# voiceboard.net
KiCad netlist of a schematic drawn in EAGLE
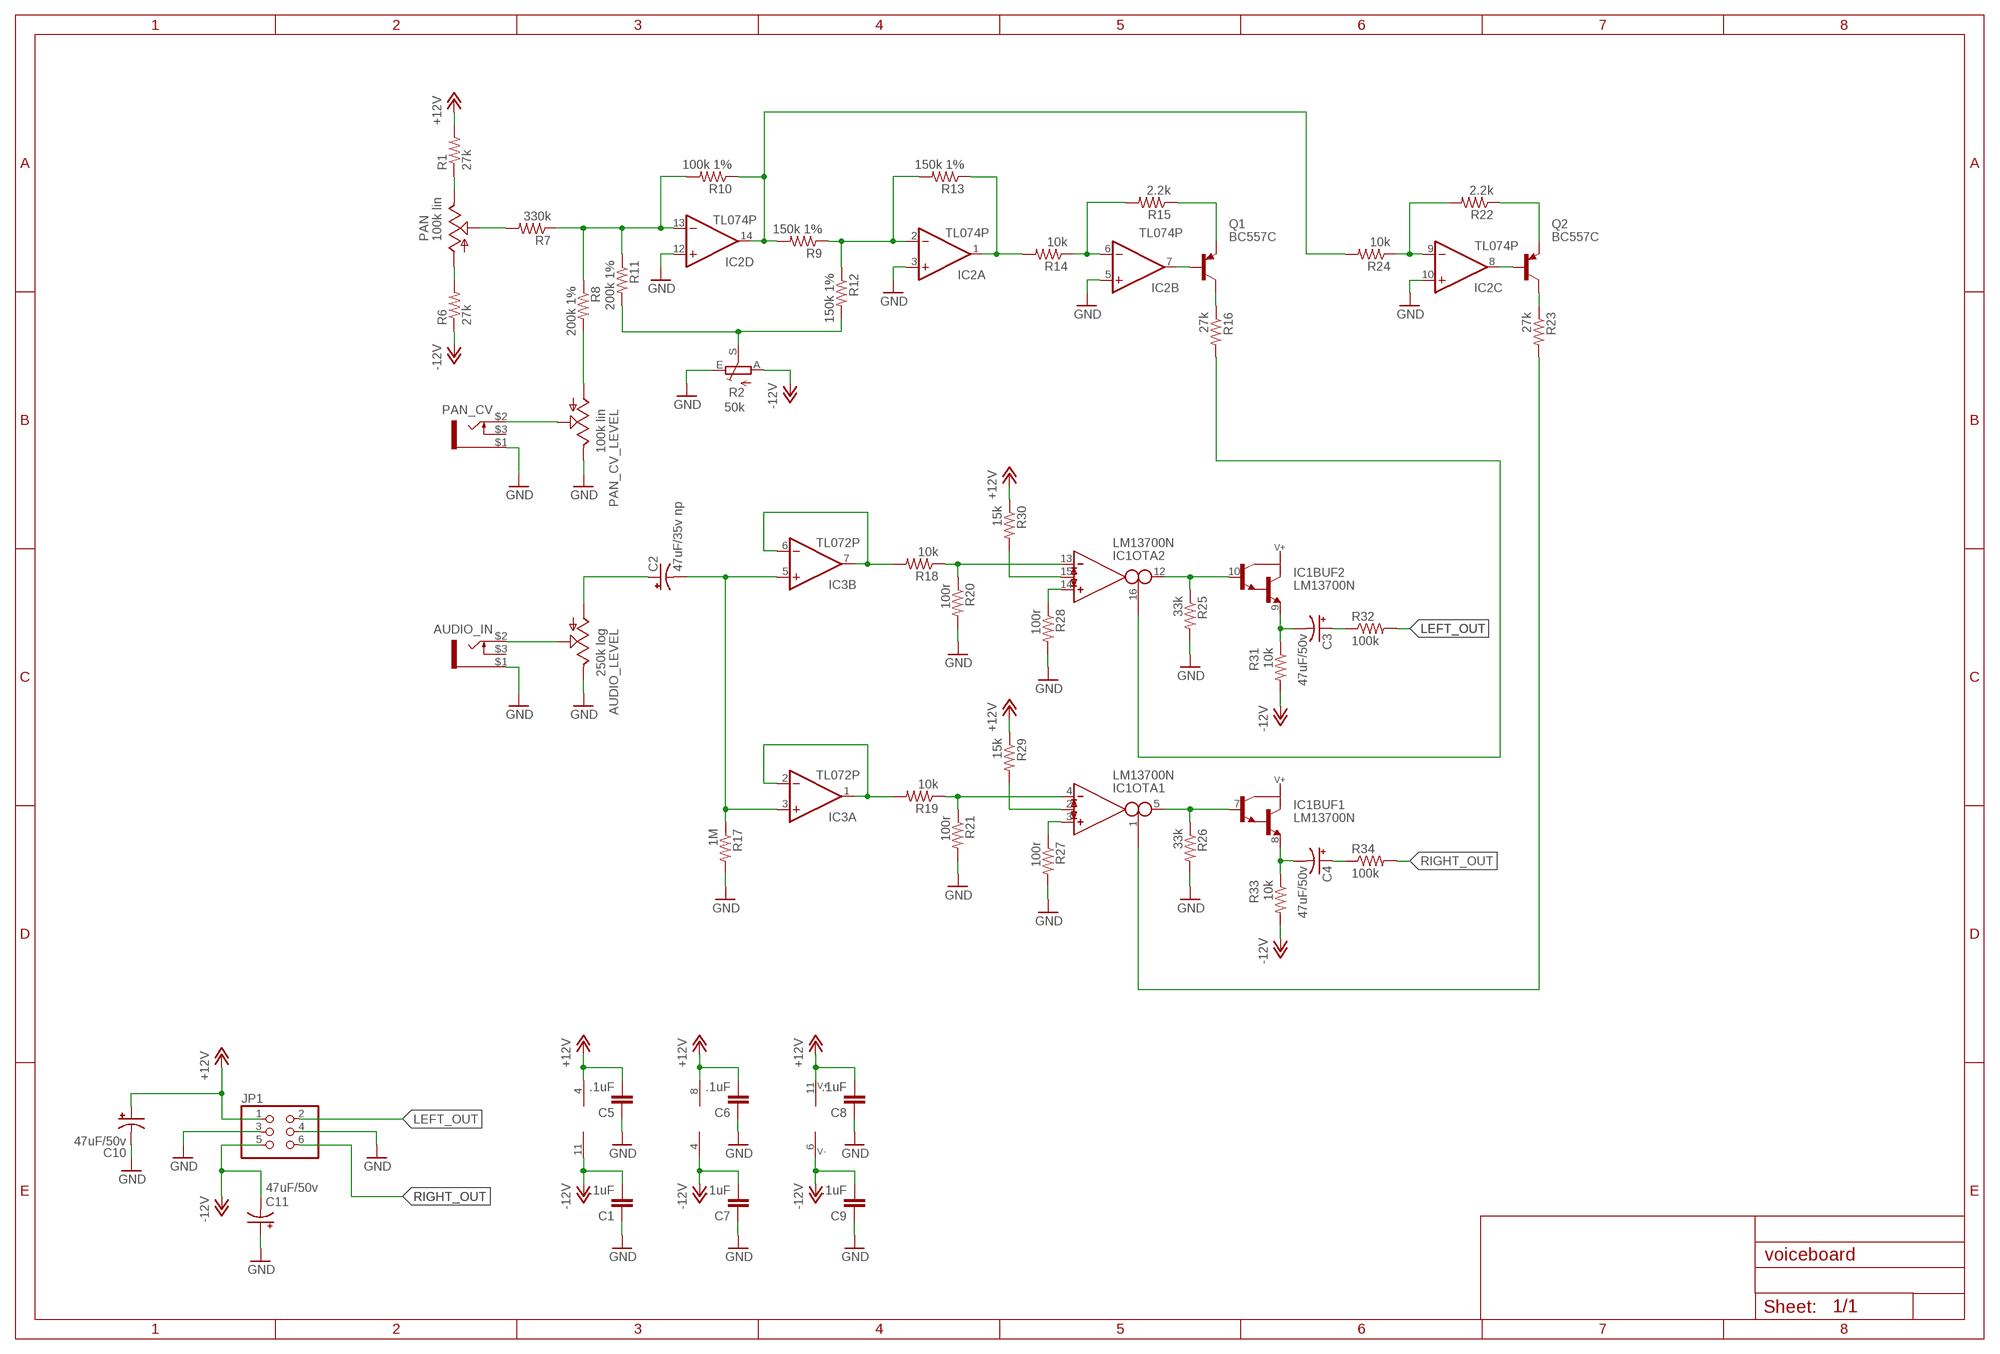
[diagram p0: schematic, sheet 1]

(export (version "E")
  (design (tool "Eeschema 10.0.6"))
  (components
    (comp (ref "AUDIO_IN")
      (value "PJ-323PJ-323")
      (footprint "eagle-import:PJ-323")
      (libsource (lib "eagle-import") (part "PJ-323PJ-323"))
    )
    (comp (ref "AUDIO_LEVEL")
      (value "250k log")
      (footprint "eagle-import:EVUF")
      (libsource (lib "eagle-import") (part "RIGHT-ANGLE-POTAF3"))
    )
    (comp (ref "C1")
      (value ".1uF")
      (footprint "eagle-import:C050-024X044")
      (libsource (lib "eagle-import") (part "C-EU050-024X044"))
    )
    (comp (ref "C2")
      (value "47uF/35v np")
      (footprint "eagle-import:E5-10,5")
      (libsource (lib "eagle-import") (part "CPOL-USE5-10.5"))
    )
    (comp (ref "C3")
      (value "47uF/50v")
      (footprint "eagle-import:E2,5-6")
      (libsource (lib "eagle-import") (part "CPOL-USE2.5-6"))
    )
    (comp (ref "C4")
      (value "47uF/50v")
      (footprint "eagle-import:E2,5-6")
      (libsource (lib "eagle-import") (part "CPOL-USE2.5-6"))
    )
    (comp (ref "C5")
      (value ".1uF")
      (footprint "eagle-import:C050-024X044")
      (libsource (lib "eagle-import") (part "C-EU050-024X044"))
    )
    (comp (ref "C6")
      (value ".1uF")
      (footprint "eagle-import:C050-024X044")
      (libsource (lib "eagle-import") (part "C-EU050-024X044"))
    )
    (comp (ref "C7")
      (value ".1uF")
      (footprint "eagle-import:C050-024X044")
      (libsource (lib "eagle-import") (part "C-EU050-024X044"))
    )
    (comp (ref "C8")
      (value ".1uF")
      (footprint "eagle-import:C050-024X044")
      (libsource (lib "eagle-import") (part "C-EU050-024X044"))
    )
    (comp (ref "C9")
      (value ".1uF")
      (footprint "eagle-import:C050-024X044")
      (libsource (lib "eagle-import") (part "C-EU050-024X044"))
    )
    (comp (ref "C10")
      (value "47uF/50v")
      (footprint "eagle-import:E2,5-6")
      (libsource (lib "eagle-import") (part "CPOL-USE2.5-6"))
    )
    (comp (ref "C11")
      (value "47uF/50v")
      (footprint "eagle-import:E2,5-6")
      (libsource (lib "eagle-import") (part "CPOL-USE2.5-6"))
    )
    (comp (ref "IC1")
      (value "LM13700N")
      (footprint "eagle-import:DIL16")
      (libsource (lib "eagle-import") (part "LM13700N"))
    )
    (comp (ref "IC2")
      (value "TL074P")
      (footprint "eagle-import:DIL14")
      (libsource (lib "eagle-import") (part "TL074P"))
    )
    (comp (ref "IC3")
      (value "TL072P")
      (footprint "eagle-import:DIL08")
      (libsource (lib "eagle-import") (part "TL072P"))
    )
    (comp (ref "JP1")
      (value "PINHD-2X3/90")
      (footprint "eagle-import:2X03_90")
      (libsource (lib "eagle-import") (part "PINHD-2X3/90"))
    )
    (comp (ref "PAN")
      (value "100k lin")
      (footprint "eagle-import:EVUF")
      (libsource (lib "eagle-import") (part "RIGHT-ANGLE-POTAF3"))
    )
    (comp (ref "PAN_CV")
      (value "PJ-323PJ-323")
      (footprint "eagle-import:PJ-323")
      (libsource (lib "eagle-import") (part "PJ-323PJ-323"))
    )
    (comp (ref "PAN_CV_LEVEL")
      (value "100k lin")
      (footprint "eagle-import:EVUF")
      (libsource (lib "eagle-import") (part "RIGHT-ANGLE-POTAF3"))
    )
    (comp (ref "Q1")
      (value "BC557C")
      (footprint "eagle-import:TO92-EBC")
      (libsource (lib "eagle-import") (part "BC557C"))
    )
    (comp (ref "Q2")
      (value "BC557C")
      (footprint "eagle-import:TO92-EBC")
      (libsource (lib "eagle-import") (part "BC557C"))
    )
    (comp (ref "R1")
      (value "27k")
      (footprint "eagle-import:0207_7")
      (libsource (lib "eagle-import") (part "R-US_0207/7"))
    )
    (comp (ref "R2")
      (value "50k")
      (footprint "eagle-import:S64YW")
      (libsource (lib "eagle-import") (part "TRIM_1234-S64YW"))
    )
    (comp (ref "R6")
      (value "27k")
      (footprint "eagle-import:0207_7")
      (libsource (lib "eagle-import") (part "R-US_0207/7"))
    )
    (comp (ref "R7")
      (value "330k")
      (footprint "eagle-import:0207_7")
      (libsource (lib "eagle-import") (part "R-US_0207/7"))
    )
    (comp (ref "R8")
      (value "200k 1%")
      (footprint "eagle-import:0207_7")
      (libsource (lib "eagle-import") (part "R-US_0207/7"))
    )
    (comp (ref "R9")
      (value "150k 1%")
      (footprint "eagle-import:0207_7")
      (libsource (lib "eagle-import") (part "R-US_0207/7"))
    )
    (comp (ref "R10")
      (value "100k 1%")
      (footprint "eagle-import:0207_7")
      (libsource (lib "eagle-import") (part "R-US_0207/7"))
    )
    (comp (ref "R11")
      (value "200k 1%")
      (footprint "eagle-import:0207_7")
      (libsource (lib "eagle-import") (part "R-US_0207/7"))
    )
    (comp (ref "R12")
      (value "150k 1%")
      (footprint "eagle-import:0207_7")
      (libsource (lib "eagle-import") (part "R-US_0207/7"))
    )
    (comp (ref "R13")
      (value "150k 1%")
      (footprint "eagle-import:0207_7")
      (libsource (lib "eagle-import") (part "R-US_0207/7"))
    )
    (comp (ref "R14")
      (value "10k")
      (footprint "eagle-import:0207_7")
      (libsource (lib "eagle-import") (part "R-US_0207/7"))
    )
    (comp (ref "R15")
      (value "2.2k")
      (footprint "eagle-import:0207_7")
      (libsource (lib "eagle-import") (part "R-US_0207/7"))
    )
    (comp (ref "R16")
      (value "27k")
      (footprint "eagle-import:0207_7")
      (libsource (lib "eagle-import") (part "R-US_0207/7"))
    )
    (comp (ref "R17")
      (value "1M")
      (footprint "eagle-import:0207_7")
      (libsource (lib "eagle-import") (part "R-US_0207/7"))
    )
    (comp (ref "R18")
      (value "10k")
      (footprint "eagle-import:0207_7")
      (libsource (lib "eagle-import") (part "R-US_0207/7"))
    )
    (comp (ref "R19")
      (value "10k")
      (footprint "eagle-import:0207_7")
      (libsource (lib "eagle-import") (part "R-US_0207/7"))
    )
    (comp (ref "R20")
      (value "100r")
      (footprint "eagle-import:0207_7")
      (libsource (lib "eagle-import") (part "R-US_0207/7"))
    )
    (comp (ref "R21")
      (value "100r")
      (footprint "eagle-import:0207_7")
      (libsource (lib "eagle-import") (part "R-US_0207/7"))
    )
    (comp (ref "R22")
      (value "2.2k")
      (footprint "eagle-import:0207_7")
      (libsource (lib "eagle-import") (part "R-US_0207/7"))
    )
    (comp (ref "R23")
      (value "27k")
      (footprint "eagle-import:0207_7")
      (libsource (lib "eagle-import") (part "R-US_0207/7"))
    )
    (comp (ref "R24")
      (value "10k")
      (footprint "eagle-import:0207_7")
      (libsource (lib "eagle-import") (part "R-US_0207/7"))
    )
    (comp (ref "R25")
      (value "33k")
      (footprint "eagle-import:0207_7")
      (libsource (lib "eagle-import") (part "R-US_0207/7"))
    )
    (comp (ref "R26")
      (value "33k")
      (footprint "eagle-import:0207_7")
      (libsource (lib "eagle-import") (part "R-US_0207/7"))
    )
    (comp (ref "R27")
      (value "100r")
      (footprint "eagle-import:0207_7")
      (libsource (lib "eagle-import") (part "R-US_0207/7"))
    )
    (comp (ref "R28")
      (value "100r")
      (footprint "eagle-import:0207_7")
      (libsource (lib "eagle-import") (part "R-US_0207/7"))
    )
    (comp (ref "R29")
      (value "15k")
      (footprint "eagle-import:0207_7")
      (libsource (lib "eagle-import") (part "R-US_0207/7"))
    )
    (comp (ref "R30")
      (value "15k")
      (footprint "eagle-import:0207_7")
      (libsource (lib "eagle-import") (part "R-US_0207/7"))
    )
    (comp (ref "R31")
      (value "10k")
      (footprint "eagle-import:0207_7")
      (libsource (lib "eagle-import") (part "R-US_0207/7"))
    )
    (comp (ref "R32")
      (value "100k")
      (footprint "eagle-import:0207_7")
      (libsource (lib "eagle-import") (part "R-US_0207/7"))
    )
    (comp (ref "R33")
      (value "10k")
      (footprint "eagle-import:0207_7")
      (libsource (lib "eagle-import") (part "R-US_0207/7"))
    )
    (comp (ref "R34")
      (value "100k")
      (footprint "eagle-import:0207_7")
      (libsource (lib "eagle-import") (part "R-US_0207/7"))
    )
  )
  (nets
    (net (code "1") (name "+12V") (class "Default")
      (node (ref "C10") (pin "+") (pinfunction "+_+") (pintype "passive"))
      (node (ref "C5") (pin "2") (pinfunction "2_2") (pintype "passive"))
      (node (ref "C6") (pin "2") (pinfunction "2_2") (pintype "passive"))
      (node (ref "C8") (pin "2") (pinfunction "2_2") (pintype "passive"))
      (node (ref "IC1") (pin "11") (pinfunction "V+_11") (pintype "power_in"))
      (node (ref "IC2") (pin "4") (pinfunction "V+_4") (pintype "power_in"))
      (node (ref "IC3") (pin "8") (pinfunction "V+_8") (pintype "power_in"))
      (node (ref "JP1") (pin "1") (pinfunction "1_1") (pintype "passive"))
      (node (ref "R1") (pin "2") (pinfunction "2_2") (pintype "passive"))
      (node (ref "R29") (pin "1") (pinfunction "1_1") (pintype "passive"))
      (node (ref "R30") (pin "1") (pinfunction "1_1") (pintype "passive"))
    )
    (net (code "2") (name "-12V") (class "Default")
      (node (ref "C1") (pin "2") (pinfunction "2_2") (pintype "passive"))
      (node (ref "C11") (pin "-") (pinfunction "-_-") (pintype "passive"))
      (node (ref "C7") (pin "2") (pinfunction "2_2") (pintype "passive"))
      (node (ref "C9") (pin "2") (pinfunction "2_2") (pintype "passive"))
      (node (ref "IC1") (pin "6") (pinfunction "V-_6") (pintype "power_in"))
      (node (ref "IC2") (pin "11") (pinfunction "V-_11") (pintype "power_in"))
      (node (ref "IC3") (pin "4") (pinfunction "V-_4") (pintype "power_in"))
      (node (ref "JP1") (pin "5") (pinfunction "5_5") (pintype "passive"))
      (node (ref "R2") (pin "A") (pinfunction "A_A") (pintype "passive"))
      (node (ref "R31") (pin "2") (pinfunction "2_2") (pintype "passive"))
      (node (ref "R33") (pin "2") (pinfunction "2_2") (pintype "passive"))
      (node (ref "R6") (pin "1") (pinfunction "1_1") (pintype "passive"))
    )
    (net (code "3") (name "GND") (class "Default")
      (node (ref "AUDIO_IN") (pin "$1") (pinfunction "3_$1") (pintype "passive"))
      (node (ref "AUDIO_LEVEL") (pin "3") (pinfunction "E_3") (pintype "passive"))
      (node (ref "C1") (pin "1") (pinfunction "1_1") (pintype "passive"))
      (node (ref "C10") (pin "-") (pinfunction "-_-") (pintype "passive"))
      (node (ref "C11") (pin "+") (pinfunction "+_+") (pintype "passive"))
      (node (ref "C5") (pin "1") (pinfunction "1_1") (pintype "passive"))
      (node (ref "C6") (pin "1") (pinfunction "1_1") (pintype "passive"))
      (node (ref "C7") (pin "1") (pinfunction "1_1") (pintype "passive"))
      (node (ref "C8") (pin "1") (pinfunction "1_1") (pintype "passive"))
      (node (ref "C9") (pin "1") (pinfunction "1_1") (pintype "passive"))
      (node (ref "IC2") (pin "10") (pinfunction "+IN_10") (pintype "input"))
      (node (ref "IC2") (pin "12") (pinfunction "+IN_12") (pintype "input"))
      (node (ref "IC2") (pin "3") (pinfunction "+IN_3") (pintype "input"))
      (node (ref "IC2") (pin "5") (pinfunction "+IN_5") (pintype "input"))
      (node (ref "JP1") (pin "3") (pinfunction "3_3") (pintype "passive"))
      (node (ref "JP1") (pin "4") (pinfunction "4_4") (pintype "passive"))
      (node (ref "PAN_CV") (pin "$1") (pinfunction "3_$1") (pintype "passive"))
      (node (ref "PAN_CV_LEVEL") (pin "3") (pinfunction "E_3") (pintype "passive"))
      (node (ref "R17") (pin "2") (pinfunction "2_2") (pintype "passive"))
      (node (ref "R2") (pin "E") (pinfunction "E_E") (pintype "passive"))
      (node (ref "R20") (pin "2") (pinfunction "2_2") (pintype "passive"))
      (node (ref "R21") (pin "2") (pinfunction "2_2") (pintype "passive"))
      (node (ref "R25") (pin "2") (pinfunction "2_2") (pintype "passive"))
      (node (ref "R26") (pin "2") (pinfunction "2_2") (pintype "passive"))
      (node (ref "R27") (pin "2") (pinfunction "2_2") (pintype "passive"))
      (node (ref "R28") (pin "2") (pinfunction "2_2") (pintype "passive"))
    )
    (net (code "4") (name "LEFT_OUT") (class "Default")
      (node (ref "JP1") (pin "2") (pinfunction "2_2") (pintype "passive"))
      (node (ref "R32") (pin "2") (pinfunction "2_2") (pintype "passive"))
    )
    (net (code "5") (name "Net-(AUDIO_IN-1)") (class "Default")
      (node (ref "AUDIO_IN") (pin "$2") (pinfunction "1_$2") (pintype "passive"))
      (node (ref "AUDIO_LEVEL") (pin "2") (pinfunction "S_2") (pintype "passive"))
    )
    (net (code "6") (name "Net-(AUDIO_LEVEL-A)") (class "Default")
      (node (ref "AUDIO_LEVEL") (pin "1") (pinfunction "A_1") (pintype "passive"))
      (node (ref "C2") (pin "+") (pinfunction "+_+") (pintype "passive"))
    )
    (net (code "7") (name "Net-(C3-Pad+)") (class "Default")
      (node (ref "C3") (pin "+") (pinfunction "+_+") (pintype "passive"))
      (node (ref "R32") (pin "1") (pinfunction "1_1") (pintype "passive"))
    )
    (net (code "8") (name "Net-(C4-Pad+)") (class "Default")
      (node (ref "C4") (pin "+") (pinfunction "+_+") (pintype "passive"))
      (node (ref "R34") (pin "1") (pinfunction "1_1") (pintype "passive"))
    )
    (net (code "9") (name "Net-(IC1A-B)") (class "Default")
      (node (ref "IC1") (pin "5") (pinfunction "OUT_5") (pintype "output"))
      (node (ref "IC1") (pin "7") (pinfunction "B_7") (pintype "passive"))
      (node (ref "R26") (pin "1") (pinfunction "1_1") (pintype "passive"))
    )
    (net (code "10") (name "Net-(IC1A-E)") (class "Default")
      (node (ref "C4") (pin "-") (pinfunction "-_-") (pintype "passive"))
      (node (ref "IC1") (pin "8") (pinfunction "E_8") (pintype "passive"))
      (node (ref "R33") (pin "1") (pinfunction "1_1") (pintype "passive"))
    )
    (net (code "11") (name "Net-(IC1B-B)") (class "Default")
      (node (ref "IC1") (pin "10") (pinfunction "B_10") (pintype "passive"))
      (node (ref "IC1") (pin "12") (pinfunction "OUT_12") (pintype "output"))
      (node (ref "R25") (pin "1") (pinfunction "1_1") (pintype "passive"))
    )
    (net (code "12") (name "Net-(IC1B-E)") (class "Default")
      (node (ref "C3") (pin "-") (pinfunction "-_-") (pintype "passive"))
      (node (ref "IC1") (pin "9") (pinfunction "E_9") (pintype "passive"))
      (node (ref "R31") (pin "1") (pinfunction "1_1") (pintype "passive"))
    )
    (net (code "13") (name "Net-(IC1C-IN_N)") (class "Default")
      (node (ref "IC1") (pin "4") (pinfunction "IN_N_4") (pintype "input"))
      (node (ref "R19") (pin "1") (pinfunction "1_1") (pintype "passive"))
      (node (ref "R21") (pin "1") (pinfunction "1_1") (pintype "passive"))
    )
    (net (code "14") (name "Net-(IC1C-IN_P)") (class "Default")
      (node (ref "IC1") (pin "3") (pinfunction "IN_P_3") (pintype "input"))
      (node (ref "R27") (pin "1") (pinfunction "1_1") (pintype "passive"))
    )
    (net (code "15") (name "Net-(IC1C-I_BIAS)") (class "Default")
      (node (ref "IC1") (pin "1") (pinfunction "I_BIAS_1") (pintype "input"))
      (node (ref "R23") (pin "2") (pinfunction "2_2") (pintype "passive"))
    )
    (net (code "16") (name "Net-(IC1C-I_DIODE)") (class "Default")
      (node (ref "IC1") (pin "2") (pinfunction "I_DIODE_2") (pintype "input"))
      (node (ref "R29") (pin "2") (pinfunction "2_2") (pintype "passive"))
    )
    (net (code "17") (name "Net-(IC1D-IN_N)") (class "Default")
      (node (ref "IC1") (pin "13") (pinfunction "IN_N_13") (pintype "input"))
      (node (ref "R18") (pin "1") (pinfunction "1_1") (pintype "passive"))
      (node (ref "R20") (pin "1") (pinfunction "1_1") (pintype "passive"))
    )
    (net (code "18") (name "Net-(IC1D-IN_P)") (class "Default")
      (node (ref "IC1") (pin "14") (pinfunction "IN_P_14") (pintype "input"))
      (node (ref "R28") (pin "1") (pinfunction "1_1") (pintype "passive"))
    )
    (net (code "19") (name "Net-(IC1D-I_BIAS)") (class "Default")
      (node (ref "IC1") (pin "16") (pinfunction "I_BIAS_16") (pintype "input"))
      (node (ref "R16") (pin "2") (pinfunction "2_2") (pintype "passive"))
    )
    (net (code "20") (name "Net-(IC1D-I_DIODE)") (class "Default")
      (node (ref "IC1") (pin "15") (pinfunction "I_DIODE_15") (pintype "input"))
      (node (ref "R30") (pin "2") (pinfunction "2_2") (pintype "passive"))
    )
    (net (code "21") (name "Net-(IC2A--IN)") (class "Default")
      (node (ref "IC2") (pin "2") (pinfunction "-IN_2") (pintype "input"))
      (node (ref "R12") (pin "1") (pinfunction "1_1") (pintype "passive"))
      (node (ref "R13") (pin "2") (pinfunction "2_2") (pintype "passive"))
      (node (ref "R9") (pin "1") (pinfunction "1_1") (pintype "passive"))
    )
    (net (code "22") (name "Net-(IC2A-OUT)") (class "Default")
      (node (ref "IC2") (pin "1") (pinfunction "OUT_1") (pintype "output"))
      (node (ref "R13") (pin "1") (pinfunction "1_1") (pintype "passive"))
      (node (ref "R14") (pin "2") (pinfunction "2_2") (pintype "passive"))
    )
    (net (code "23") (name "Net-(IC2B--IN)") (class "Default")
      (node (ref "IC2") (pin "6") (pinfunction "-IN_6") (pintype "input"))
      (node (ref "R14") (pin "1") (pinfunction "1_1") (pintype "passive"))
      (node (ref "R15") (pin "2") (pinfunction "2_2") (pintype "passive"))
    )
    (net (code "24") (name "Net-(IC2B-OUT)") (class "Default")
      (node (ref "IC2") (pin "7") (pinfunction "OUT_7") (pintype "output"))
      (node (ref "Q1") (pin "B") (pinfunction "B_B") (pintype "passive"))
    )
    (net (code "25") (name "Net-(IC2C--IN)") (class "Default")
      (node (ref "IC2") (pin "9") (pinfunction "-IN_9") (pintype "input"))
      (node (ref "R22") (pin "2") (pinfunction "2_2") (pintype "passive"))
      (node (ref "R24") (pin "1") (pinfunction "1_1") (pintype "passive"))
    )
    (net (code "26") (name "Net-(IC2C-OUT)") (class "Default")
      (node (ref "IC2") (pin "8") (pinfunction "OUT_8") (pintype "output"))
      (node (ref "Q2") (pin "B") (pinfunction "B_B") (pintype "passive"))
    )
    (net (code "27") (name "Net-(IC2D--IN)") (class "Default")
      (node (ref "IC2") (pin "13") (pinfunction "-IN_13") (pintype "input"))
      (node (ref "R10") (pin "2") (pinfunction "2_2") (pintype "passive"))
      (node (ref "R11") (pin "1") (pinfunction "1_1") (pintype "passive"))
      (node (ref "R7") (pin "1") (pinfunction "1_1") (pintype "passive"))
      (node (ref "R8") (pin "1") (pinfunction "1_1") (pintype "passive"))
    )
    (net (code "28") (name "Net-(IC2D-OUT)") (class "Default")
      (node (ref "IC2") (pin "14") (pinfunction "OUT_14") (pintype "output"))
      (node (ref "R10") (pin "1") (pinfunction "1_1") (pintype "passive"))
      (node (ref "R24") (pin "2") (pinfunction "2_2") (pintype "passive"))
      (node (ref "R9") (pin "2") (pinfunction "2_2") (pintype "passive"))
    )
    (net (code "29") (name "Net-(IC3A-+IN)") (class "Default")
      (node (ref "C2") (pin "-") (pinfunction "-_-") (pintype "passive"))
      (node (ref "IC3") (pin "3") (pinfunction "+IN_3") (pintype "input"))
      (node (ref "IC3") (pin "5") (pinfunction "+IN_5") (pintype "input"))
      (node (ref "R17") (pin "1") (pinfunction "1_1") (pintype "passive"))
    )
    (net (code "30") (name "Net-(IC3A--IN)") (class "Default")
      (node (ref "IC3") (pin "1") (pinfunction "OUT_1") (pintype "output"))
      (node (ref "IC3") (pin "2") (pinfunction "-IN_2") (pintype "input"))
      (node (ref "R19") (pin "2") (pinfunction "2_2") (pintype "passive"))
    )
    (net (code "31") (name "Net-(IC3B--IN)") (class "Default")
      (node (ref "IC3") (pin "6") (pinfunction "-IN_6") (pintype "input"))
      (node (ref "IC3") (pin "7") (pinfunction "OUT_7") (pintype "output"))
      (node (ref "R18") (pin "2") (pinfunction "2_2") (pintype "passive"))
    )
    (net (code "32") (name "Net-(PAN-A)") (class "Default")
      (node (ref "PAN") (pin "1") (pinfunction "A_1") (pintype "passive"))
      (node (ref "R6") (pin "2") (pinfunction "2_2") (pintype "passive"))
    )
    (net (code "33") (name "Net-(PAN-E)") (class "Default")
      (node (ref "PAN") (pin "3") (pinfunction "E_3") (pintype "passive"))
      (node (ref "R1") (pin "1") (pinfunction "1_1") (pintype "passive"))
    )
    (net (code "34") (name "Net-(PAN-S)") (class "Default")
      (node (ref "PAN") (pin "2") (pinfunction "S_2") (pintype "passive"))
      (node (ref "R7") (pin "2") (pinfunction "2_2") (pintype "passive"))
    )
    (net (code "35") (name "Net-(PAN_CV-1)") (class "Default")
      (node (ref "PAN_CV") (pin "$2") (pinfunction "1_$2") (pintype "passive"))
      (node (ref "PAN_CV_LEVEL") (pin "2") (pinfunction "S_2") (pintype "passive"))
    )
    (net (code "36") (name "Net-(PAN_CV_LEVEL-A)") (class "Default")
      (node (ref "PAN_CV_LEVEL") (pin "1") (pinfunction "A_1") (pintype "passive"))
      (node (ref "R8") (pin "2") (pinfunction "2_2") (pintype "passive"))
    )
    (net (code "37") (name "Net-(Q1-PadC)") (class "Default")
      (node (ref "Q1") (pin "C") (pinfunction "C_C") (pintype "passive"))
      (node (ref "R16") (pin "1") (pinfunction "1_1") (pintype "passive"))
    )
    (net (code "38") (name "Net-(Q1-PadE)") (class "Default")
      (node (ref "Q1") (pin "E") (pinfunction "E_E") (pintype "passive"))
      (node (ref "R15") (pin "1") (pinfunction "1_1") (pintype "passive"))
    )
    (net (code "39") (name "Net-(Q2-PadC)") (class "Default")
      (node (ref "Q2") (pin "C") (pinfunction "C_C") (pintype "passive"))
      (node (ref "R23") (pin "1") (pinfunction "1_1") (pintype "passive"))
    )
    (net (code "40") (name "Net-(Q2-PadE)") (class "Default")
      (node (ref "Q2") (pin "E") (pinfunction "E_E") (pintype "passive"))
      (node (ref "R22") (pin "1") (pinfunction "1_1") (pintype "passive"))
    )
    (net (code "41") (name "Net-(R11-Pad2)") (class "Default")
      (node (ref "R11") (pin "2") (pinfunction "2_2") (pintype "passive"))
      (node (ref "R12") (pin "2") (pinfunction "2_2") (pintype "passive"))
      (node (ref "R2") (pin "S") (pinfunction "S_S") (pintype "passive"))
    )
    (net (code "42") (name "RIGHT_OUT") (class "Default")
      (node (ref "JP1") (pin "6") (pinfunction "6_6") (pintype "passive"))
      (node (ref "R34") (pin "2") (pinfunction "2_2") (pintype "passive"))
    )
    (net (code "43") (name "unconnected-(AUDIO_IN-2-Pad$3)") (class "Default")
      (node (ref "AUDIO_IN") (pin "$3") (pinfunction "2_$3") (pintype "passive"))
    )
    (net (code "44") (name "unconnected-(PAN_CV-2-Pad$3)") (class "Default")
      (node (ref "PAN_CV") (pin "$3") (pinfunction "2_$3") (pintype "passive"))
    )
    (net (code "45") (name "unconnected-(R2-S-PadS@1)") (class "Default")
      (node (ref "R2") (pin "S@1") (pinfunction "S_S@1") (pintype "passive"))
    )
  )
)
